# Sheet1.net
KiCad netlist of a schematic drawn in Altium Designer
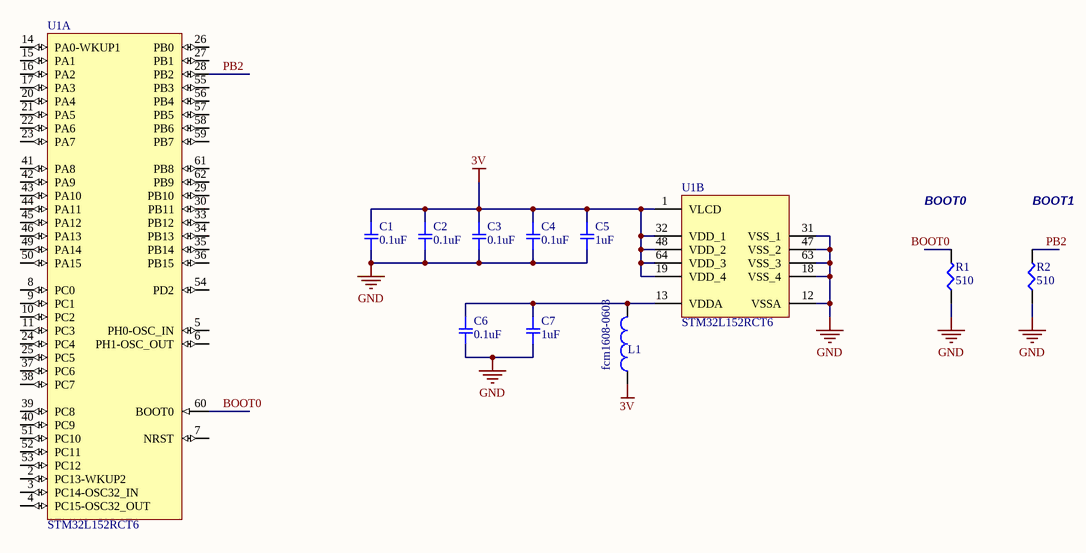
[diagram p0: Sheet1.SchDoc]

(export (version "E")
  (design (tool "Eeschema 10.0.6"))
  (components
    (comp (ref "C1")
      (value "0.1uF")
      (footprint "SMD-0805C")
      (description "CAP CER 0.1uF 50V X7T 0805")
      (fields
        (field (name "PART NUMBER") "GC321AD72E103KX01D")
        (field (name "MANUFACTURER") "Samsung Electro-Mechanics")
      )
      (libsource (lib "capacitor_0805") (part "CL21B104JBCNNNC"))
    )
    (comp (ref "C2")
      (value "0.1uF")
      (footprint "SMD-0805C")
      (description "CAP CER 0.1uF 50V X7T 0805")
      (fields
        (field (name "PART NUMBER") "GC321AD72E103KX01D")
        (field (name "MANUFACTURER") "Samsung Electro-Mechanics")
      )
      (libsource (lib "capacitor_0805") (part "CL21B104JBCNNNC"))
    )
    (comp (ref "C3")
      (value "0.1uF")
      (footprint "SMD-0805C")
      (description "CAP CER 0.1uF 50V X7T 0805")
      (fields
        (field (name "PART NUMBER") "GC321AD72E103KX01D")
        (field (name "MANUFACTURER") "Samsung Electro-Mechanics")
      )
      (libsource (lib "capacitor_0805") (part "CL21B104JBCNNNC"))
    )
    (comp (ref "C4")
      (value "0.1uF")
      (footprint "SMD-0805C")
      (description "CAP CER 0.1uF 50V X7T 0805")
      (fields
        (field (name "PART NUMBER") "GC321AD72E103KX01D")
        (field (name "MANUFACTURER") "Samsung Electro-Mechanics")
      )
      (libsource (lib "capacitor_0805") (part "CL21B104JBCNNNC"))
    )
    (comp (ref "C5")
      (value "1uF")
      (footprint "SMD-0805C")
      (description "CAP CER 1uF 16V X7T 0805")
      (fields
        (field (name "PART NUMBER") "CL21B105KOFNNNG")
        (field (name "MANUFACTURER") "Samsung Electro-Mechanics")
      )
      (libsource (lib "capacitor_0805") (part "CL21B105KOFNNNG"))
    )
    (comp (ref "C6")
      (value "0.1uF")
      (footprint "SMD-0805C")
      (description "CAP CER 0.1uF 50V X7T 0805")
      (fields
        (field (name "PART NUMBER") "GC321AD72E103KX01D")
        (field (name "MANUFACTURER") "Samsung Electro-Mechanics")
      )
      (libsource (lib "capacitor_0805") (part "CL21B104JBCNNNC"))
    )
    (comp (ref "C7")
      (value "1uF")
      (footprint "SMD-0805C")
      (description "CAP CER 1uF 16V X7T 0805")
      (fields
        (field (name "PART NUMBER") "CL21B105KOFNNNG")
        (field (name "MANUFACTURER") "Samsung Electro-Mechanics")
      )
      (libsource (lib "capacitor_0805") (part "CL21B105KOFNNNG"))
    )
    (comp (ref "L1")
      (value "fcm1608-0603")
      (footprint "Miscellaneous Devices:0603")
      (description "Inductor")
      (fields (field (name "PUBLISHER") "Altium Limited"))
      (libsource (lib "Miscellaneous Devices") (part "Inductor"))
    )
    (comp (ref "R1")
      (value "510")
      (footprint "SMD-0805-RES")
      (description "RES SMD 510 OHM 5% 1/8W 0805")
      (fields (field (name "PART NUMBER") "ERJ-6GEYJ511V") (field (name "DIGI-KEY PART NUMBER") "P510ACT-ND"))
      (libsource (lib "Panasonic_ERJ_0805") (part "ERJ-6GEYJ511V"))
    )
    (comp (ref "R2")
      (value "510")
      (footprint "SMD-0805-RES")
      (description "RES SMD 510 OHM 5% 1/8W 0805")
      (fields (field (name "PART NUMBER") "ERJ-6GEYJ511V") (field (name "DIGI-KEY PART NUMBER") "P510ACT-ND"))
      (libsource (lib "Panasonic_ERJ_0805") (part "ERJ-6GEYJ511V"))
    )
    (comp (ref "U1")
      (value "STM32L152RCT6")
      (footprint "STM-LQFP64_L")
      (fields (field (name "MANUFACTURER") "STMicroelectronics"))
      (libsource (lib "STMicroelectronics STM32 L1") (part "STM32L152RCT6"))
    )
  )
  (nets
    (net (code "1") (name "/BOOT0") (class "Default")
      (node (ref "U1") (pin "60") (pinfunction "BOOT0_60") (pintype "input"))
    )
    (net (code "2") (name "/PB2") (class "Default")
      (node (ref "R2") (pin "2") (pinfunction "2_2") (pintype "passive"))
      (node (ref "U1") (pin "28") (pinfunction "PB2_28") (pintype "bidirectional"))
    )
    (net (code "3") (name "3V") (class "Default")
      (node (ref "C1") (pin "1") (pinfunction "1_1") (pintype "passive"))
      (node (ref "C2") (pin "1") (pinfunction "1_1") (pintype "passive"))
      (node (ref "C3") (pin "1") (pinfunction "1_1") (pintype "passive"))
      (node (ref "C4") (pin "1") (pinfunction "1_1") (pintype "passive"))
      (node (ref "C5") (pin "1") (pinfunction "1_1") (pintype "passive"))
      (node (ref "L1") (pin "1") (pinfunction "1_1") (pintype "passive"))
      (node (ref "U1") (pin "1") (pinfunction "VLCD_1") (pintype "power_in"))
      (node (ref "U1") (pin "19") (pinfunction "VDD_4_19") (pintype "power_in"))
      (node (ref "U1") (pin "32") (pinfunction "VDD_1_32") (pintype "power_in"))
      (node (ref "U1") (pin "48") (pinfunction "VDD_2_48") (pintype "power_in"))
      (node (ref "U1") (pin "64") (pinfunction "VDD_3_64") (pintype "power_in"))
    )
    (net (code "4") (name "GND") (class "Default")
      (node (ref "C1") (pin "2") (pinfunction "2_2") (pintype "passive"))
      (node (ref "C2") (pin "2") (pinfunction "2_2") (pintype "passive"))
      (node (ref "C3") (pin "2") (pinfunction "2_2") (pintype "passive"))
      (node (ref "C4") (pin "2") (pinfunction "2_2") (pintype "passive"))
      (node (ref "C5") (pin "2") (pinfunction "2_2") (pintype "passive"))
      (node (ref "C6") (pin "2") (pinfunction "2_2") (pintype "passive"))
      (node (ref "C7") (pin "2") (pinfunction "2_2") (pintype "passive"))
      (node (ref "R1") (pin "1") (pinfunction "1_1") (pintype "passive"))
      (node (ref "R2") (pin "1") (pinfunction "1_1") (pintype "passive"))
      (node (ref "U1") (pin "12") (pinfunction "VSSA_12") (pintype "power_in"))
      (node (ref "U1") (pin "18") (pinfunction "VSS_4_18") (pintype "power_in"))
      (node (ref "U1") (pin "31") (pinfunction "VSS_1_31") (pintype "power_in"))
      (node (ref "U1") (pin "47") (pinfunction "VSS_2_47") (pintype "power_in"))
      (node (ref "U1") (pin "63") (pinfunction "VSS_3_63") (pintype "power_in"))
    )
    (net (code "5") (name "Net-(U1B-VDDA)") (class "Default")
      (node (ref "C6") (pin "1") (pinfunction "1_1") (pintype "passive"))
      (node (ref "C7") (pin "1") (pinfunction "1_1") (pintype "passive"))
      (node (ref "L1") (pin "2") (pinfunction "2_2") (pintype "passive"))
      (node (ref "U1") (pin "13") (pinfunction "VDDA_13") (pintype "power_in"))
    )
    (net (code "6") (name "unconnected-(R1-Pad2)") (class "Default")
      (node (ref "R1") (pin "2") (pinfunction "2_2") (pintype "passive"))
    )
    (net (code "7") (name "unconnected-(U1A-NRST-Pad7)") (class "Default")
      (node (ref "U1") (pin "7") (pinfunction "NRST_7") (pintype "bidirectional"))
    )
    (net (code "8") (name "unconnected-(U1A-PA0-WKUP1-Pad14)") (class "Default")
      (node (ref "U1") (pin "14") (pinfunction "PA0-WKUP1_14") (pintype "bidirectional"))
    )
    (net (code "9") (name "unconnected-(U1A-PA1-Pad15)") (class "Default")
      (node (ref "U1") (pin "15") (pinfunction "PA1_15") (pintype "bidirectional"))
    )
    (net (code "10") (name "unconnected-(U1A-PA2-Pad16)") (class "Default")
      (node (ref "U1") (pin "16") (pinfunction "PA2_16") (pintype "bidirectional"))
    )
    (net (code "11") (name "unconnected-(U1A-PA3-Pad17)") (class "Default")
      (node (ref "U1") (pin "17") (pinfunction "PA3_17") (pintype "bidirectional"))
    )
    (net (code "12") (name "unconnected-(U1A-PA4-Pad20)") (class "Default")
      (node (ref "U1") (pin "20") (pinfunction "PA4_20") (pintype "bidirectional"))
    )
    (net (code "13") (name "unconnected-(U1A-PA5-Pad21)") (class "Default")
      (node (ref "U1") (pin "21") (pinfunction "PA5_21") (pintype "bidirectional"))
    )
    (net (code "14") (name "unconnected-(U1A-PA6-Pad22)") (class "Default")
      (node (ref "U1") (pin "22") (pinfunction "PA6_22") (pintype "bidirectional"))
    )
    (net (code "15") (name "unconnected-(U1A-PA7-Pad23)") (class "Default")
      (node (ref "U1") (pin "23") (pinfunction "PA7_23") (pintype "bidirectional"))
    )
    (net (code "16") (name "unconnected-(U1A-PA8-Pad41)") (class "Default")
      (node (ref "U1") (pin "41") (pinfunction "PA8_41") (pintype "bidirectional"))
    )
    (net (code "17") (name "unconnected-(U1A-PA9-Pad42)") (class "Default")
      (node (ref "U1") (pin "42") (pinfunction "PA9_42") (pintype "bidirectional"))
    )
    (net (code "18") (name "unconnected-(U1A-PA10-Pad43)") (class "Default")
      (node (ref "U1") (pin "43") (pinfunction "PA10_43") (pintype "bidirectional"))
    )
    (net (code "19") (name "unconnected-(U1A-PA11-Pad44)") (class "Default")
      (node (ref "U1") (pin "44") (pinfunction "PA11_44") (pintype "bidirectional"))
    )
    (net (code "20") (name "unconnected-(U1A-PA12-Pad45)") (class "Default")
      (node (ref "U1") (pin "45") (pinfunction "PA12_45") (pintype "bidirectional"))
    )
    (net (code "21") (name "unconnected-(U1A-PA13-Pad46)") (class "Default")
      (node (ref "U1") (pin "46") (pinfunction "PA13_46") (pintype "bidirectional"))
    )
    (net (code "22") (name "unconnected-(U1A-PA14-Pad49)") (class "Default")
      (node (ref "U1") (pin "49") (pinfunction "PA14_49") (pintype "bidirectional"))
    )
    (net (code "23") (name "unconnected-(U1A-PA15-Pad50)") (class "Default")
      (node (ref "U1") (pin "50") (pinfunction "PA15_50") (pintype "bidirectional"))
    )
    (net (code "24") (name "unconnected-(U1A-PB0-Pad26)") (class "Default")
      (node (ref "U1") (pin "26") (pinfunction "PB0_26") (pintype "bidirectional"))
    )
    (net (code "25") (name "unconnected-(U1A-PB1-Pad27)") (class "Default")
      (node (ref "U1") (pin "27") (pinfunction "PB1_27") (pintype "bidirectional"))
    )
    (net (code "26") (name "unconnected-(U1A-PB3-Pad55)") (class "Default")
      (node (ref "U1") (pin "55") (pinfunction "PB3_55") (pintype "bidirectional"))
    )
    (net (code "27") (name "unconnected-(U1A-PB4-Pad56)") (class "Default")
      (node (ref "U1") (pin "56") (pinfunction "PB4_56") (pintype "bidirectional"))
    )
    (net (code "28") (name "unconnected-(U1A-PB5-Pad57)") (class "Default")
      (node (ref "U1") (pin "57") (pinfunction "PB5_57") (pintype "bidirectional"))
    )
    (net (code "29") (name "unconnected-(U1A-PB6-Pad58)") (class "Default")
      (node (ref "U1") (pin "58") (pinfunction "PB6_58") (pintype "bidirectional"))
    )
    (net (code "30") (name "unconnected-(U1A-PB7-Pad59)") (class "Default")
      (node (ref "U1") (pin "59") (pinfunction "PB7_59") (pintype "bidirectional"))
    )
    (net (code "31") (name "unconnected-(U1A-PB8-Pad61)") (class "Default")
      (node (ref "U1") (pin "61") (pinfunction "PB8_61") (pintype "bidirectional"))
    )
    (net (code "32") (name "unconnected-(U1A-PB9-Pad62)") (class "Default")
      (node (ref "U1") (pin "62") (pinfunction "PB9_62") (pintype "bidirectional"))
    )
    (net (code "33") (name "unconnected-(U1A-PB10-Pad29)") (class "Default")
      (node (ref "U1") (pin "29") (pinfunction "PB10_29") (pintype "bidirectional"))
    )
    (net (code "34") (name "unconnected-(U1A-PB11-Pad30)") (class "Default")
      (node (ref "U1") (pin "30") (pinfunction "PB11_30") (pintype "bidirectional"))
    )
    (net (code "35") (name "unconnected-(U1A-PB12-Pad33)") (class "Default")
      (node (ref "U1") (pin "33") (pinfunction "PB12_33") (pintype "bidirectional"))
    )
    (net (code "36") (name "unconnected-(U1A-PB13-Pad34)") (class "Default")
      (node (ref "U1") (pin "34") (pinfunction "PB13_34") (pintype "bidirectional"))
    )
    (net (code "37") (name "unconnected-(U1A-PB14-Pad35)") (class "Default")
      (node (ref "U1") (pin "35") (pinfunction "PB14_35") (pintype "bidirectional"))
    )
    (net (code "38") (name "unconnected-(U1A-PB15-Pad36)") (class "Default")
      (node (ref "U1") (pin "36") (pinfunction "PB15_36") (pintype "bidirectional"))
    )
    (net (code "39") (name "unconnected-(U1A-PC0-Pad8)") (class "Default")
      (node (ref "U1") (pin "8") (pinfunction "PC0_8") (pintype "bidirectional"))
    )
    (net (code "40") (name "unconnected-(U1A-PC1-Pad9)") (class "Default")
      (node (ref "U1") (pin "9") (pinfunction "PC1_9") (pintype "bidirectional"))
    )
    (net (code "41") (name "unconnected-(U1A-PC2-Pad10)") (class "Default")
      (node (ref "U1") (pin "10") (pinfunction "PC2_10") (pintype "bidirectional"))
    )
    (net (code "42") (name "unconnected-(U1A-PC3-Pad11)") (class "Default")
      (node (ref "U1") (pin "11") (pinfunction "PC3_11") (pintype "bidirectional"))
    )
    (net (code "43") (name "unconnected-(U1A-PC4-Pad24)") (class "Default")
      (node (ref "U1") (pin "24") (pinfunction "PC4_24") (pintype "bidirectional"))
    )
    (net (code "44") (name "unconnected-(U1A-PC5-Pad25)") (class "Default")
      (node (ref "U1") (pin "25") (pinfunction "PC5_25") (pintype "bidirectional"))
    )
    (net (code "45") (name "unconnected-(U1A-PC6-Pad37)") (class "Default")
      (node (ref "U1") (pin "37") (pinfunction "PC6_37") (pintype "bidirectional"))
    )
    (net (code "46") (name "unconnected-(U1A-PC7-Pad38)") (class "Default")
      (node (ref "U1") (pin "38") (pinfunction "PC7_38") (pintype "bidirectional"))
    )
    (net (code "47") (name "unconnected-(U1A-PC8-Pad39)") (class "Default")
      (node (ref "U1") (pin "39") (pinfunction "PC8_39") (pintype "bidirectional"))
    )
    (net (code "48") (name "unconnected-(U1A-PC9-Pad40)") (class "Default")
      (node (ref "U1") (pin "40") (pinfunction "PC9_40") (pintype "bidirectional"))
    )
    (net (code "49") (name "unconnected-(U1A-PC10-Pad51)") (class "Default")
      (node (ref "U1") (pin "51") (pinfunction "PC10_51") (pintype "bidirectional"))
    )
    (net (code "50") (name "unconnected-(U1A-PC11-Pad52)") (class "Default")
      (node (ref "U1") (pin "52") (pinfunction "PC11_52") (pintype "bidirectional"))
    )
    (net (code "51") (name "unconnected-(U1A-PC12-Pad53)") (class "Default")
      (node (ref "U1") (pin "53") (pinfunction "PC12_53") (pintype "bidirectional"))
    )
    (net (code "52") (name "unconnected-(U1A-PC13-WKUP2-Pad2)") (class "Default")
      (node (ref "U1") (pin "2") (pinfunction "PC13-WKUP2_2") (pintype "bidirectional"))
    )
    (net (code "53") (name "unconnected-(U1A-PC14-OSC32_IN-Pad3)") (class "Default")
      (node (ref "U1") (pin "3") (pinfunction "PC14-OSC32_IN_3") (pintype "bidirectional"))
    )
    (net (code "54") (name "unconnected-(U1A-PC15-OSC32_OUT-Pad4)") (class "Default")
      (node (ref "U1") (pin "4") (pinfunction "PC15-OSC32_OUT_4") (pintype "bidirectional"))
    )
    (net (code "55") (name "unconnected-(U1A-PD2-Pad54)") (class "Default")
      (node (ref "U1") (pin "54") (pinfunction "PD2_54") (pintype "bidirectional"))
    )
    (net (code "56") (name "unconnected-(U1A-PH0-OSC_IN-Pad5)") (class "Default")
      (node (ref "U1") (pin "5") (pinfunction "PH0-OSC_IN_5") (pintype "bidirectional"))
    )
    (net (code "57") (name "unconnected-(U1A-PH1-OSC_OUT-Pad6)") (class "Default")
      (node (ref "U1") (pin "6") (pinfunction "PH1-OSC_OUT_6") (pintype "bidirectional"))
    )
  )
)
